# DoomsdayPCB.net
KiCad netlist of a schematic drawn in EAGLE
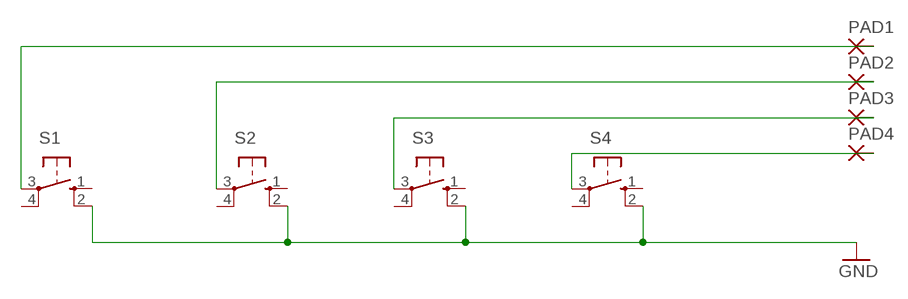
[diagram p0: schematic, sheet 1]

(export (version "E")
  (design (tool "Eeschema 10.0.6"))
  (components
    (comp (ref "PAD1")
      (value "2,54/1,0")
      (footprint "eagle-import:2,54_1,0")
      (libsource (lib "eagle-import") (part "2,54/1,0"))
    )
    (comp (ref "PAD2")
      (value "2,54/1,0")
      (footprint "eagle-import:2,54_1,0")
      (libsource (lib "eagle-import") (part "2,54/1,0"))
    )
    (comp (ref "PAD3")
      (value "2,54/1,0")
      (footprint "eagle-import:2,54_1,0")
      (libsource (lib "eagle-import") (part "2,54/1,0"))
    )
    (comp (ref "PAD4")
      (value "2,54/1,0")
      (footprint "eagle-import:2,54_1,0")
      (libsource (lib "eagle-import") (part "2,54/1,0"))
    )
    (comp (ref "S1")
      (value "40-XX")
      (footprint "eagle-import:B3F-40XX")
      (fields (field (name "MF") "OMRON COMPONENTS USA") (field (name "MPN") "B3F-4000"))
      (libsource (lib "eagle-import") (part "40-XX"))
    )
    (comp (ref "S2")
      (value "40-XX")
      (footprint "eagle-import:B3F-40XX")
      (fields (field (name "MF") "OMRON COMPONENTS USA") (field (name "MPN") "B3F-4000"))
      (libsource (lib "eagle-import") (part "40-XX"))
    )
    (comp (ref "S3")
      (value "40-XX")
      (footprint "eagle-import:B3F-40XX")
      (fields (field (name "MF") "OMRON COMPONENTS USA") (field (name "MPN") "B3F-4000"))
      (libsource (lib "eagle-import") (part "40-XX"))
    )
    (comp (ref "S4")
      (value "40-XX")
      (footprint "eagle-import:B3F-40XX")
      (fields (field (name "MF") "OMRON COMPONENTS USA") (field (name "MPN") "B3F-4000"))
      (libsource (lib "eagle-import") (part "40-XX"))
    )
  )
  (nets
    (net (code "1") (name "GND") (class "Default")
      (node (ref "S1") (pin "2") (pinfunction "S1_2") (pintype "passive"))
      (node (ref "S2") (pin "2") (pinfunction "S1_2") (pintype "passive"))
      (node (ref "S3") (pin "2") (pinfunction "S1_2") (pintype "passive"))
      (node (ref "S4") (pin "2") (pinfunction "S1_2") (pintype "passive"))
    )
    (net (code "2") (name "Net-(PAD1-P)") (class "Default")
      (node (ref "PAD1") (pin "1") (pinfunction "P_1") (pintype "passive"))
      (node (ref "S1") (pin "3") (pinfunction "P_3") (pintype "passive"))
    )
    (net (code "3") (name "Net-(PAD2-P)") (class "Default")
      (node (ref "PAD2") (pin "1") (pinfunction "P_1") (pintype "passive"))
      (node (ref "S2") (pin "3") (pinfunction "P_3") (pintype "passive"))
    )
    (net (code "4") (name "Net-(PAD3-P)") (class "Default")
      (node (ref "PAD3") (pin "1") (pinfunction "P_1") (pintype "passive"))
      (node (ref "S3") (pin "3") (pinfunction "P_3") (pintype "passive"))
    )
    (net (code "5") (name "Net-(PAD4-P)") (class "Default")
      (node (ref "PAD4") (pin "1") (pinfunction "P_1") (pintype "passive"))
      (node (ref "S4") (pin "3") (pinfunction "P_3") (pintype "passive"))
    )
    (net (code "6") (name "unconnected-(S1-P1-Pad4)") (class "Default")
      (node (ref "S1") (pin "4") (pinfunction "P1_4") (pintype "passive"))
    )
    (net (code "7") (name "unconnected-(S1-S-Pad1)") (class "Default")
      (node (ref "S1") (pin "1") (pinfunction "S_1") (pintype "passive"))
    )
    (net (code "8") (name "unconnected-(S2-P1-Pad4)") (class "Default")
      (node (ref "S2") (pin "4") (pinfunction "P1_4") (pintype "passive"))
    )
    (net (code "9") (name "unconnected-(S2-S-Pad1)") (class "Default")
      (node (ref "S2") (pin "1") (pinfunction "S_1") (pintype "passive"))
    )
    (net (code "10") (name "unconnected-(S3-P1-Pad4)") (class "Default")
      (node (ref "S3") (pin "4") (pinfunction "P1_4") (pintype "passive"))
    )
    (net (code "11") (name "unconnected-(S3-S-Pad1)") (class "Default")
      (node (ref "S3") (pin "1") (pinfunction "S_1") (pintype "passive"))
    )
    (net (code "12") (name "unconnected-(S4-P1-Pad4)") (class "Default")
      (node (ref "S4") (pin "4") (pinfunction "P1_4") (pintype "passive"))
    )
    (net (code "13") (name "unconnected-(S4-S-Pad1)") (class "Default")
      (node (ref "S4") (pin "1") (pinfunction "S_1") (pintype "passive"))
    )
  )
)
